# Overvoltage_Protection.net
KiCad netlist of a schematic drawn in Altium Designer
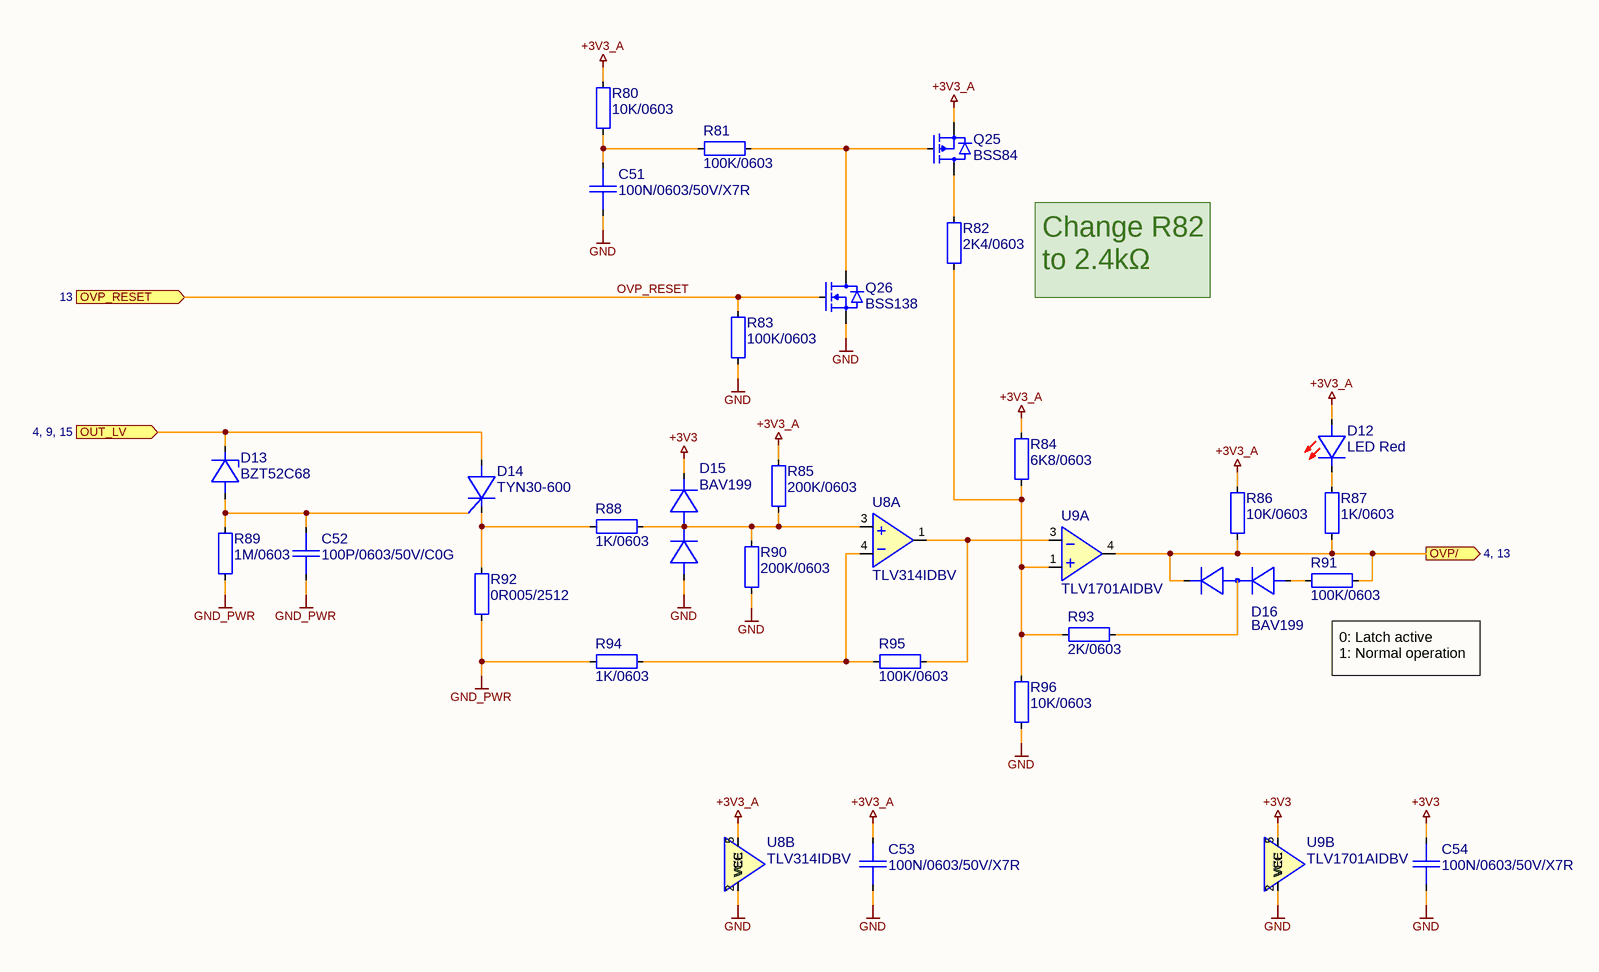
[diagram p0: Overvoltage_Protection.SchDoc]

(export (version "E")
  (design (tool "Eeschema 10.0.6"))
  (components
    (comp (ref "C51")
      (value "100N/0603/50V/X7R")
      (footprint "CAP0603_X7R")
      (description "CAP SM 0603 100nF 50V X7R")
      (fields (field (name "MANUFACTURER") "GENERIC"))
      (libsource (lib "daniw_altium_lib") (part "C"))
    )
    (comp (ref "C52")
      (value "100P/0603/50V/C0G")
      (footprint "CAP0603_C0G")
      (description "CAP SM 0603 100pF 50V C0G")
      (fields (field (name "MANUFACTURER") "GENERIC"))
      (libsource (lib "daniw_altium_lib") (part "C"))
    )
    (comp (ref "C53")
      (value "100N/0603/50V/X7R")
      (footprint "CAP0603_X7R")
      (description "CAP SM 0603 100nF 50V X7R")
      (fields (field (name "MANUFACTURER") "GENERIC"))
      (libsource (lib "daniw_altium_lib") (part "C"))
    )
    (comp (ref "C54")
      (value "100N/0603/50V/X7R")
      (footprint "CAP0603_X7R")
      (description "CAP SM 0603 100nF 50V X7R")
      (fields (field (name "MANUFACTURER") "GENERIC"))
      (libsource (lib "daniw_altium_lib") (part "C"))
    )
    (comp (ref "D12")
      (value "LED Red")
      (footprint "LED0805_RED")
      (description "Generic LED Red 0805")
      (fields (field (name "PART NUMBER") "LED Red 0805") (field (name "MANUFACTURER") "GENERIC"))
      (libsource (lib "daniw_altium_lib") (part "LED_RED"))
    )
    (comp (ref "D13")
      (value "BZT52C68")
      (footprint "SOD3718X125")
      (description "DIODE ZENER 68V 350MW SOD123")
      (fields (field (name "MANUFACTURER") "Nexperia USA Inc."))
      (libsource (lib "daniw_altium_lib") (part "D_Zener"))
    )
    (comp (ref "D14")
      (value "TYN30-600")
      (footprint "TO220-3")
      (description "Planar passivated Silicon Controlled Rectifier (SCR) in a TO220 plastic package, 600V, 30A")
      (fields (field (name "MANUFACTURER") "WeEn Semiconductors"))
      (libsource (lib "daniw_altium_lib") (part "SCR_1K_2A_3G"))
    )
    (comp (ref "D15")
      (value "BAV199")
      (footprint "SOT2395P280X125-3-SE")
      (description "Silicon Low Leakage Diode 85V")
      (fields (field (name "MANUFACTURER") "Infineon Technologies"))
      (libsource (lib "daniw_altium_lib") (part "D_Serie"))
    )
    (comp (ref "D16")
      (value "BAV199")
      (footprint "SOT2395P280X125-3-SE")
      (description "Silicon Low Leakage Diode 85V")
      (fields (field (name "MANUFACTURER") "Infineon Technologies"))
      (libsource (lib "daniw_altium_lib") (part "D_Serie"))
    )
    (comp (ref "Q25")
      (value "BSS84")
      (footprint "SOT2395P280X125-3-SE")
      (description "50V P-Channel MOSFET")
      (fields (field (name "MANUFACTURER") "GENERIC"))
      (libsource (lib "daniw_altium_lib") (part "MOSFET_P_G1_D3_S2"))
    )
    (comp (ref "Q26")
      (value "BSS138")
      (footprint "SOT2395P280X125-3-SE")
      (description "N-Kanal 50 V 220mA (Ta) 350mW (Ta) Oberflächenmontage SOT-23")
      (fields (field (name "MANUFACTURER") "GENERIC"))
      (libsource (lib "daniw_altium_lib") (part "MOSFET_N_G1_D3_S2"))
    )
    (comp (ref "R80")
      (value "10K/0603")
      (footprint "R0603-0.40-WW")
      (description "RES SM 0603 10K")
      (fields (field (name "MANUFACTURER") "GENERIC"))
      (libsource (lib "daniw_altium_lib") (part "R"))
    )
    (comp (ref "R81")
      (value "100K/0603")
      (footprint "R0603-0.40-WW")
      (description "RES SM 0603 100K")
      (fields (field (name "MANUFACTURER") "GENERIC"))
      (libsource (lib "daniw_altium_lib") (part "R"))
    )
    (comp (ref "R82")
      (value "2K4/0603")
      (footprint "R0603-0.40-WW")
      (description "RES SM 0603 2K4")
      (fields (field (name "MANUFACTURER") "GENERIC"))
      (libsource (lib "daniw_altium_lib") (part "R"))
    )
    (comp (ref "R83")
      (value "100K/0603")
      (footprint "R0603-0.40-WW")
      (description "RES SM 0603 100K")
      (fields (field (name "MANUFACTURER") "GENERIC"))
      (libsource (lib "daniw_altium_lib") (part "R"))
    )
    (comp (ref "R84")
      (value "6K8/0603")
      (footprint "R0603-0.40-WW")
      (description "RES SM 0603 6K8")
      (fields (field (name "MANUFACTURER") "GENERIC"))
      (libsource (lib "daniw_altium_lib") (part "R"))
    )
    (comp (ref "R85")
      (value "200K/0603")
      (footprint "R0603-0.40-WW")
      (description "RES SM 0603 200K")
      (fields (field (name "MANUFACTURER") "GENERIC"))
      (libsource (lib "daniw_altium_lib") (part "R"))
    )
    (comp (ref "R86")
      (value "10K/0603")
      (footprint "R0603-0.40-WW")
      (description "RES SM 0603 10K")
      (fields (field (name "MANUFACTURER") "GENERIC"))
      (libsource (lib "daniw_altium_lib") (part "R"))
    )
    (comp (ref "R87")
      (value "1K/0603")
      (footprint "R0603-0.40-WW")
      (description "RES SM 0603 1K")
      (fields (field (name "MANUFACTURER") "GENERIC"))
      (libsource (lib "daniw_altium_lib") (part "R"))
    )
    (comp (ref "R88")
      (value "1K/0603")
      (footprint "R0603-0.40-WW")
      (description "RES SM 0603 1K")
      (fields (field (name "MANUFACTURER") "GENERIC"))
      (libsource (lib "daniw_altium_lib") (part "R"))
    )
    (comp (ref "R89")
      (value "1M/0603")
      (footprint "R0603-0.40-WW")
      (description "RES SM 0603 1M")
      (fields (field (name "MANUFACTURER") "GENERIC"))
      (libsource (lib "daniw_altium_lib") (part "R"))
    )
    (comp (ref "R90")
      (value "200K/0603")
      (footprint "R0603-0.40-WW")
      (description "RES SM 0603 200K")
      (fields (field (name "MANUFACTURER") "GENERIC"))
      (libsource (lib "daniw_altium_lib") (part "R"))
    )
    (comp (ref "R91")
      (value "100K/0603")
      (footprint "R0603-0.40-WW")
      (description "RES SM 0603 100K")
      (fields (field (name "MANUFACTURER") "GENERIC"))
      (libsource (lib "daniw_altium_lib") (part "R"))
    )
    (comp (ref "R92")
      (value "0R005/2512")
      (footprint "R2512-0.65-WW")
      (description "RES SM 2512 0R005")
      (fields (field (name "MANUFACTURER") "GENERIC"))
      (libsource (lib "daniw_altium_lib") (part "R"))
    )
    (comp (ref "R93")
      (value "2K/0603")
      (footprint "R0603-0.40-WW")
      (description "RES SM 0603 2K")
      (fields (field (name "MANUFACTURER") "GENERIC"))
      (libsource (lib "daniw_altium_lib") (part "R"))
    )
    (comp (ref "R94")
      (value "1K/0603")
      (footprint "R0603-0.40-WW")
      (description "RES SM 0603 1K")
      (fields (field (name "MANUFACTURER") "GENERIC"))
      (libsource (lib "daniw_altium_lib") (part "R"))
    )
    (comp (ref "R95")
      (value "100K/0603")
      (footprint "R0603-0.40-WW")
      (description "RES SM 0603 100K")
      (fields (field (name "MANUFACTURER") "GENERIC"))
      (libsource (lib "daniw_altium_lib") (part "R"))
    )
    (comp (ref "R96")
      (value "10K/0603")
      (footprint "R0603-0.40-WW")
      (description "RES SM 0603 10K")
      (fields (field (name "MANUFACTURER") "GENERIC"))
      (libsource (lib "daniw_altium_lib") (part "R"))
    )
    (comp (ref "U8")
      (value "TLV314IDBV")
      (footprint "SOT2395P280X125-5-NW")
      (description "TLV314, 3-MHz, Low-Power, Internal EMI Filter, RRIO, Operational Amplifier")
      (fields (field (name "PART NUMBER") "TLV314 SOT23") (field (name "MANUFACTURER") "Texas Instruments"))
      (libsource (lib "daniw_altium_lib") (part "OPA_O1_P3_N4_VCC5_VEE2"))
    )
    (comp (ref "U9")
      (value "TLV1701AIDBV")
      (footprint "SOT2395P280X125-5-NW")
      (description "TLV1701 2.2-V to 36-V, microPower Comparato")
      (fields (field (name "PART NUMBER") "TLV1701 SOT23") (field (name "MANUFACTURER") "Texas Instruments"))
      (libsource (lib "daniw_altium_lib") (part "OPA_O4_P1_N3_VCC5_VEE2"))
    )
  )
  (nets
    (net (code "1") (name "+3V3") (class "Default")
      (node (ref "C54") (pin "1") (pinfunction "1_1") (pintype "passive"))
      (node (ref "D15") (pin "2") (pinfunction "K2_2") (pintype "passive"))
      (node (ref "U9") (pin "5") (pinfunction "VCC_5") (pintype "passive"))
    )
    (net (code "2") (name "+3V3_A") (class "Default")
      (node (ref "C53") (pin "1") (pinfunction "1_1") (pintype "passive"))
      (node (ref "D12") (pin "2") (pinfunction "A_2") (pintype "passive"))
      (node (ref "Q25") (pin "2") (pinfunction "SOURCE_2") (pintype "passive"))
      (node (ref "R80") (pin "1") (pinfunction "1_1") (pintype "passive"))
      (node (ref "R84") (pin "1") (pinfunction "1_1") (pintype "passive"))
      (node (ref "R85") (pin "1") (pinfunction "1_1") (pintype "passive"))
      (node (ref "R86") (pin "2") (pinfunction "2_2") (pintype "passive"))
      (node (ref "U8") (pin "5") (pinfunction "VCC_5") (pintype "passive"))
    )
    (net (code "3") (name "/OUT_LV") (class "Default")
      (node (ref "D13") (pin "1") (pinfunction "C_1") (pintype "passive"))
      (node (ref "D14") (pin "2") (pinfunction "A_2") (pintype "passive"))
    )
    (net (code "4") (name "/OVP_RESET") (class "Default")
      (node (ref "Q26") (pin "1") (pinfunction "GATE_1") (pintype "passive"))
      (node (ref "R83") (pin "1") (pinfunction "1_1") (pintype "passive"))
    )
    (net (code "5") (name "/OVP{slash}") (class "Default")
      (node (ref "D16") (pin "2") (pinfunction "K2_2") (pintype "passive"))
      (node (ref "R86") (pin "1") (pinfunction "1_1") (pintype "passive"))
      (node (ref "R87") (pin "1") (pinfunction "1_1") (pintype "passive"))
      (node (ref "R91") (pin "2") (pinfunction "2_2") (pintype "passive"))
      (node (ref "U9") (pin "4") (pinfunction "OUT_4") (pintype "passive"))
    )
    (net (code "6") (name "GND") (class "Default")
      (node (ref "C51") (pin "2") (pinfunction "2_2") (pintype "passive"))
      (node (ref "C53") (pin "2") (pinfunction "2_2") (pintype "passive"))
      (node (ref "C54") (pin "2") (pinfunction "2_2") (pintype "passive"))
      (node (ref "D15") (pin "1") (pinfunction "A1_1") (pintype "passive"))
      (node (ref "Q26") (pin "2") (pinfunction "SOURCE_2") (pintype "passive"))
      (node (ref "R83") (pin "2") (pinfunction "2_2") (pintype "passive"))
      (node (ref "R90") (pin "2") (pinfunction "2_2") (pintype "passive"))
      (node (ref "R96") (pin "2") (pinfunction "2_2") (pintype "passive"))
      (node (ref "U8") (pin "2") (pinfunction "VEE_2") (pintype "passive"))
      (node (ref "U9") (pin "2") (pinfunction "VEE_2") (pintype "passive"))
    )
    (net (code "7") (name "GND_PWR") (class "Default")
      (node (ref "C52") (pin "2") (pinfunction "2_2") (pintype "passive"))
      (node (ref "R89") (pin "2") (pinfunction "2_2") (pintype "passive"))
      (node (ref "R92") (pin "2") (pinfunction "2_2") (pintype "passive"))
      (node (ref "R94") (pin "2") (pinfunction "2_2") (pintype "passive"))
    )
    (net (code "8") (name "Net-(C51-Pad1)") (class "Default")
      (node (ref "C51") (pin "1") (pinfunction "1_1") (pintype "passive"))
      (node (ref "R80") (pin "2") (pinfunction "2_2") (pintype "passive"))
      (node (ref "R81") (pin "1") (pinfunction "1_1") (pintype "passive"))
    )
    (net (code "9") (name "Net-(D12-C)") (class "Default")
      (node (ref "D12") (pin "1") (pinfunction "C_1") (pintype "passive"))
      (node (ref "R87") (pin "2") (pinfunction "2_2") (pintype "passive"))
    )
    (net (code "10") (name "Net-(D13-A)") (class "Default")
      (node (ref "C52") (pin "1") (pinfunction "1_1") (pintype "passive"))
      (node (ref "D13") (pin "2") (pinfunction "A_2") (pintype "passive"))
      (node (ref "D14") (pin "3") (pinfunction "G_3") (pintype "passive"))
      (node (ref "R89") (pin "1") (pinfunction "1_1") (pintype "passive"))
    )
    (net (code "11") (name "Net-(D14-C)") (class "Default")
      (node (ref "D14") (pin "1") (pinfunction "C_1") (pintype "passive"))
      (node (ref "R88") (pin "1") (pinfunction "1_1") (pintype "passive"))
      (node (ref "R92") (pin "1") (pinfunction "1_1") (pintype "passive"))
    )
    (net (code "12") (name "Net-(D15-K1{slash}A2)") (class "Default")
      (node (ref "D15") (pin "3") (pinfunction "K1/A2_3") (pintype "passive"))
      (node (ref "R85") (pin "2") (pinfunction "2_2") (pintype "passive"))
      (node (ref "R88") (pin "2") (pinfunction "2_2") (pintype "passive"))
      (node (ref "R90") (pin "1") (pinfunction "1_1") (pintype "passive"))
      (node (ref "U8") (pin "3") (pinfunction "IN+_3") (pintype "passive"))
    )
    (net (code "13") (name "Net-(D16-A1)") (class "Default")
      (node (ref "D16") (pin "1") (pinfunction "A1_1") (pintype "passive"))
      (node (ref "R91") (pin "1") (pinfunction "1_1") (pintype "passive"))
    )
    (net (code "14") (name "Net-(D16-K1{slash}A2)") (class "Default")
      (node (ref "D16") (pin "3") (pinfunction "K1/A2_3") (pintype "passive"))
      (node (ref "R93") (pin "2") (pinfunction "2_2") (pintype "passive"))
    )
    (net (code "15") (name "Net-(Q25-DRAIN)") (class "Default")
      (node (ref "Q25") (pin "3") (pinfunction "DRAIN_3") (pintype "passive"))
      (node (ref "R82") (pin "1") (pinfunction "1_1") (pintype "passive"))
    )
    (net (code "16") (name "Net-(Q25-GATE)") (class "Default")
      (node (ref "Q25") (pin "1") (pinfunction "GATE_1") (pintype "passive"))
      (node (ref "Q26") (pin "3") (pinfunction "DRAIN_3") (pintype "passive"))
      (node (ref "R81") (pin "2") (pinfunction "2_2") (pintype "passive"))
    )
    (net (code "17") (name "Net-(U8A-IN-)") (class "Default")
      (node (ref "R94") (pin "1") (pinfunction "1_1") (pintype "passive"))
      (node (ref "R95") (pin "2") (pinfunction "2_2") (pintype "passive"))
      (node (ref "U8") (pin "4") (pinfunction "IN-_4") (pintype "passive"))
    )
    (net (code "18") (name "Net-(U8A-OUT)") (class "Default")
      (node (ref "R95") (pin "1") (pinfunction "1_1") (pintype "passive"))
      (node (ref "U8") (pin "1") (pinfunction "OUT_1") (pintype "passive"))
      (node (ref "U9") (pin "3") (pinfunction "IN-_3") (pintype "passive"))
    )
    (net (code "19") (name "Net-(U9A-IN+)") (class "Default")
      (node (ref "R82") (pin "2") (pinfunction "2_2") (pintype "passive"))
      (node (ref "R84") (pin "2") (pinfunction "2_2") (pintype "passive"))
      (node (ref "R93") (pin "1") (pinfunction "1_1") (pintype "passive"))
      (node (ref "R96") (pin "1") (pinfunction "1_1") (pintype "passive"))
      (node (ref "U9") (pin "1") (pinfunction "IN+_1") (pintype "passive"))
    )
  )
)
